# mp28164-buck-boost-flashlight-driver-tes.net
KiCad netlist of a schematic drawn in EAGLE
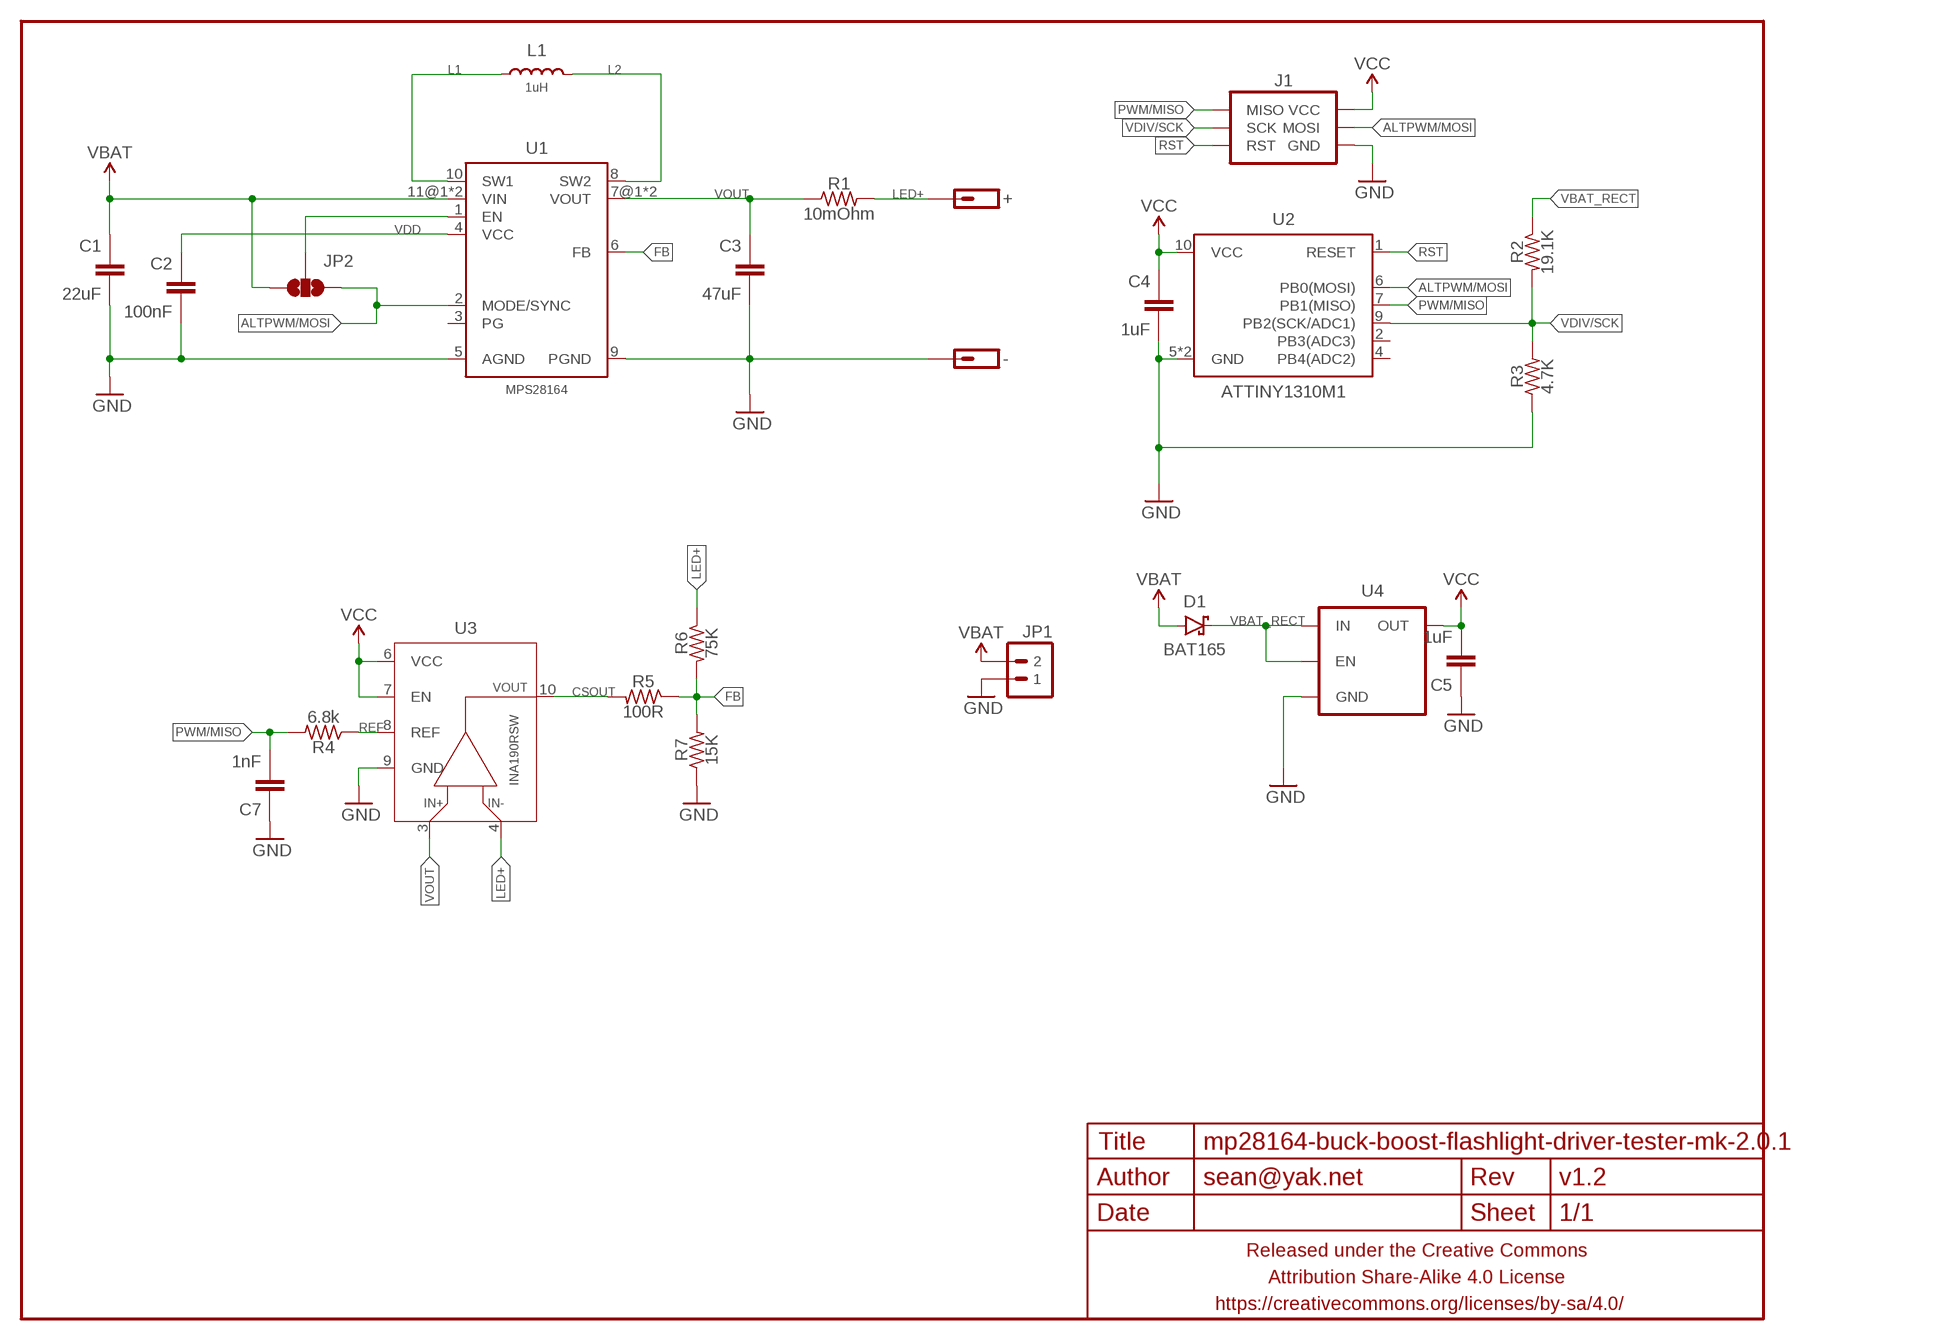
[diagram p0: schematic, sheet 1]

(export (version "E")
  (design (tool "Eeschema 10.0.6"))
  (components
    (comp (ref "+")
      (value "M01PTH-1.2MM-NS")
      (footprint "eagle-import:1X01-1.2MM-NS")
      (libsource (lib "eagle-import") (part "M01PTH-1.2MM-NS"))
    )
    (comp (ref "-")
      (value "M01PTH-1.2MM-NS")
      (footprint "eagle-import:1X01-1.2MM-NS")
      (libsource (lib "eagle-import") (part "M01PTH-1.2MM-NS"))
    )
    (comp (ref "C1")
      (value "22uF")
      (footprint "eagle-import:C1206")
      (libsource (lib "eagle-import") (part "CAPACITOR-CERAMICC1206"))
    )
    (comp (ref "C2")
      (value "100nF")
      (footprint "eagle-import:C0402")
      (libsource (lib "eagle-import") (part "CAPACITOR-CERAMICC0402"))
    )
    (comp (ref "C3")
      (value "47uF")
      (footprint "eagle-import:C1206")
      (libsource (lib "eagle-import") (part "CAPACITOR-CERAMICC1206"))
    )
    (comp (ref "C4")
      (value "1uF")
      (footprint "eagle-import:C0402")
      (libsource (lib "eagle-import") (part "CAPACITOR-CERAMICC0402"))
    )
    (comp (ref "C5")
      (value "1uF")
      (footprint "eagle-import:C0402")
      (libsource (lib "eagle-import") (part "CAPACITOR-CERAMICC0402"))
    )
    (comp (ref "C7")
      (value "1nF")
      (footprint "eagle-import:C0402")
      (libsource (lib "eagle-import") (part "CAPACITOR-CERAMICC0402"))
    )
    (comp (ref "D1")
      (value "BAT165")
      (footprint "eagle-import:SOD323-SCHOTTKY")
      (libsource (lib "eagle-import") (part "DIODE-SCHOTTKYSOD323"))
    )
    (comp (ref "FRAME1")
      (value "FRAME-LETTERNO_PACKAGE")
      (footprint "eagle-import:DUMMY")
      (fields
        (field (name "DESIGNER") "sean@yak.net")
        (field (name "VERSION") "v1.2")
        (field (name "DESIGNER_1") "sean@yak.net")
        (field (name "VERSION_1") "v1.2")
      )
      (libsource (lib "eagle-import") (part "FRAME-LETTERNO_PACKAGE"))
    )
    (comp (ref "J1")
      (value "AVR_SPI_PRG_6PTH")
      (footprint "eagle-import:2X3")
      (libsource (lib "eagle-import") (part "AVR_SPI_PRG_6PTH"))
    )
    (comp (ref "JP1")
      (value "M02PTH-CENTERED")
      (footprint "eagle-import:1X02-CENTER")
      (libsource (lib "eagle-import") (part "M02PTH-CENTERED"))
    )
    (comp (ref "JP2")
      (value "JUMPER-PAD-3-NOFULL_BOX_SILK")
      (footprint "eagle-import:PAD-JUMPER-3-NO_YES_SILK_FULL_BOX")
      (libsource (lib "eagle-import") (part "JUMPER-PAD-3-NOFULL_BOX_SILK"))
    )
    (comp (ref "L1")
      (value "1uH")
      (footprint "eagle-import:XAL60XX")
      (libsource (lib "eagle-import") (part "INDUCTORXAL60XX"))
    )
    (comp (ref "R1")
      (value "10mOhm")
      (footprint "eagle-import:R1206")
      (libsource (lib "eagle-import") (part "RESISTORR1206"))
    )
    (comp (ref "R2")
      (value "19.1K")
      (footprint "eagle-import:R0402")
      (libsource (lib "eagle-import") (part "RESISTORR0402"))
    )
    (comp (ref "R3")
      (value "4.7K")
      (footprint "eagle-import:R0402")
      (libsource (lib "eagle-import") (part "RESISTORR0402"))
    )
    (comp (ref "R4")
      (value "6.8k")
      (footprint "eagle-import:R0402")
      (libsource (lib "eagle-import") (part "RESISTORR0402"))
    )
    (comp (ref "R5")
      (value "100R")
      (footprint "eagle-import:R0402")
      (libsource (lib "eagle-import") (part "RESISTORR0402"))
    )
    (comp (ref "R6")
      (value "75K")
      (footprint "eagle-import:R0402")
      (libsource (lib "eagle-import") (part "RESISTORR0402"))
    )
    (comp (ref "R7")
      (value "15K")
      (footprint "eagle-import:R0402")
      (libsource (lib "eagle-import") (part "RESISTORR0402"))
    )
    (comp (ref "U1")
      (value "MPS28164")
      (footprint "eagle-import:MPS28164")
      (libsource (lib "eagle-import") (part "MPS28164"))
    )
    (comp (ref "U2")
      (value "ATTINY1310M1")
      (footprint "eagle-import:QFN10(2X5)")
      (libsource (lib "eagle-import") (part "ATTINY1310M1"))
    )
    (comp (ref "U3")
      (value "INA190RSW")
      (footprint "eagle-import:UQFN-10")
      (libsource (lib "eagle-import") (part "INA190RSW"))
    )
    (comp (ref "U4")
      (value "V_REG_ENTLV700")
      (footprint "eagle-import:SC70")
      (libsource (lib "eagle-import") (part "V_REG_ENTLV700"))
    )
  )
  (nets
    (net (code "1") (name "/CSOUT") (class "Default")
      (node (ref "R5") (pin "2") (pinfunction "2_2") (pintype "passive"))
      (node (ref "U3") (pin "10") (pinfunction "OUT_10") (pintype "bidirectional"))
    )
    (net (code "2") (name "/L1") (class "Default")
      (node (ref "L1") (pin "P$1") (pinfunction "1_P$1") (pintype "passive"))
      (node (ref "U1") (pin "10") (pinfunction "SW1_10") (pintype "bidirectional"))
    )
    (net (code "3") (name "/L2") (class "Default")
      (node (ref "L1") (pin "P$2") (pinfunction "2_P$2") (pintype "passive"))
      (node (ref "U1") (pin "8") (pinfunction "SW2_8") (pintype "bidirectional"))
    )
    (net (code "4") (name "/REF") (class "Default")
      (node (ref "R4") (pin "1") (pinfunction "1_1") (pintype "passive"))
      (node (ref "U3") (pin "8") (pinfunction "REF_8") (pintype "bidirectional"))
    )
    (net (code "5") (name "/VDD") (class "Default")
      (node (ref "C2") (pin "1") (pinfunction "1_1") (pintype "passive"))
      (node (ref "U1") (pin "4") (pinfunction "VCC_4") (pintype "bidirectional"))
    )
    (net (code "6") (name "ALTPWM{slash}MOSI") (class "Default")
      (node (ref "J1") (pin "4") (pinfunction "MOSI_4") (pintype "passive"))
      (node (ref "JP2") (pin "1") (pinfunction "1_1") (pintype "passive"))
      (node (ref "U1") (pin "2") (pinfunction "MODE/SYNC_2") (pintype "bidirectional"))
      (node (ref "U2") (pin "6") (pinfunction "PB0(MOSI)_6") (pintype "bidirectional"))
    )
    (net (code "7") (name "FB") (class "Default")
      (node (ref "R5") (pin "1") (pinfunction "1_1") (pintype "passive"))
      (node (ref "R6") (pin "2") (pinfunction "2_2") (pintype "passive"))
      (node (ref "R7") (pin "2") (pinfunction "2_2") (pintype "passive"))
      (node (ref "U1") (pin "6") (pinfunction "FB_6") (pintype "bidirectional"))
    )
    (net (code "8") (name "GND") (class "Default")
      (node (ref "-") (pin "P$1") (pinfunction "1_P$1") (pintype "passive"))
      (node (ref "C1") (pin "2") (pinfunction "2_2") (pintype "passive"))
      (node (ref "C2") (pin "2") (pinfunction "2_2") (pintype "passive"))
      (node (ref "C3") (pin "2") (pinfunction "2_2") (pintype "passive"))
      (node (ref "C4") (pin "2") (pinfunction "2_2") (pintype "passive"))
      (node (ref "C5") (pin "1") (pinfunction "1_1") (pintype "passive"))
      (node (ref "C7") (pin "1") (pinfunction "1_1") (pintype "passive"))
      (node (ref "J1") (pin "6") (pinfunction "GND_6") (pintype "passive"))
      (node (ref "JP1") (pin "1") (pinfunction "1_1") (pintype "passive"))
      (node (ref "R3") (pin "1") (pinfunction "1_1") (pintype "passive"))
      (node (ref "R7") (pin "1") (pinfunction "1_1") (pintype "passive"))
      (node (ref "U1") (pin "5") (pinfunction "AGND_5") (pintype "bidirectional"))
      (node (ref "U1") (pin "9") (pinfunction "PGND_9") (pintype "bidirectional"))
      (node (ref "U2") (pin "5") (pinfunction "GND_5") (pintype "bidirectional"))
      (node (ref "U2") (pin "PAD") (pinfunction "GND_PAD") (pintype "bidirectional"))
      (node (ref "U3") (pin "9") (pinfunction "GND_9") (pintype "bidirectional"))
      (node (ref "U4") (pin "2") (pinfunction "GND_2") (pintype "input"))
    )
    (net (code "9") (name "LED+") (class "Default")
      (node (ref "+") (pin "P$1") (pinfunction "1_P$1") (pintype "passive"))
      (node (ref "R1") (pin "2") (pinfunction "2_2") (pintype "passive"))
      (node (ref "R6") (pin "1") (pinfunction "1_1") (pintype "passive"))
      (node (ref "U3") (pin "4") (pinfunction "VIN-_4") (pintype "bidirectional"))
    )
    (net (code "10") (name "Net-(U1-EN)") (class "Default")
      (node (ref "JP2") (pin "2") (pinfunction "2_2") (pintype "passive"))
      (node (ref "U1") (pin "1") (pinfunction "EN_1") (pintype "bidirectional"))
    )
    (net (code "11") (name "PWM{slash}MISO") (class "Default")
      (node (ref "C7") (pin "2") (pinfunction "2_2") (pintype "passive"))
      (node (ref "J1") (pin "1") (pinfunction "MISO_1") (pintype "passive"))
      (node (ref "R4") (pin "2") (pinfunction "2_2") (pintype "passive"))
      (node (ref "U2") (pin "7") (pinfunction "PB1(MISO)_7") (pintype "bidirectional"))
    )
    (net (code "12") (name "RST") (class "Default")
      (node (ref "J1") (pin "5") (pinfunction "RST_5") (pintype "passive"))
      (node (ref "U2") (pin "1") (pinfunction "RESET_1") (pintype "bidirectional"))
    )
    (net (code "13") (name "VBAT") (class "Default")
      (node (ref "C1") (pin "1") (pinfunction "1_1") (pintype "passive"))
      (node (ref "D1") (pin "A") (pinfunction "A_A") (pintype "passive"))
      (node (ref "JP1") (pin "2") (pinfunction "2_2") (pintype "passive"))
      (node (ref "JP2") (pin "3") (pinfunction "3_3") (pintype "passive"))
      (node (ref "U1") (pin "11@1") (pinfunction "VIN_11@1") (pintype "bidirectional"))
      (node (ref "U1") (pin "11@2") (pinfunction "VIN_11@2") (pintype "bidirectional"))
    )
    (net (code "14") (name "VBAT_RECT") (class "Default")
      (node (ref "D1") (pin "C") (pinfunction "C_C") (pintype "passive"))
      (node (ref "R2") (pin "1") (pinfunction "1_1") (pintype "passive"))
      (node (ref "U4") (pin "1") (pinfunction "IN_1") (pintype "input"))
      (node (ref "U4") (pin "3") (pinfunction "EN_3") (pintype "input"))
    )
    (net (code "15") (name "VCC") (class "Default")
      (node (ref "C4") (pin "1") (pinfunction "1_1") (pintype "passive"))
      (node (ref "C5") (pin "2") (pinfunction "2_2") (pintype "passive"))
      (node (ref "J1") (pin "2") (pinfunction "VCC_2") (pintype "passive"))
      (node (ref "U2") (pin "10") (pinfunction "VCC_10") (pintype "bidirectional"))
      (node (ref "U3") (pin "6") (pinfunction "VCC_6") (pintype "bidirectional"))
      (node (ref "U3") (pin "7") (pinfunction "EN_7") (pintype "bidirectional"))
      (node (ref "U4") (pin "5") (pinfunction "OUT_5") (pintype "passive"))
    )
    (net (code "16") (name "VDIV{slash}SCK") (class "Default")
      (node (ref "J1") (pin "3") (pinfunction "SCK_3") (pintype "passive"))
      (node (ref "R2") (pin "2") (pinfunction "2_2") (pintype "passive"))
      (node (ref "R3") (pin "2") (pinfunction "2_2") (pintype "passive"))
      (node (ref "U2") (pin "9") (pinfunction "PB2(SCK/ADC1)_9") (pintype "bidirectional"))
    )
    (net (code "17") (name "VOUT") (class "Default")
      (node (ref "C3") (pin "1") (pinfunction "1_1") (pintype "passive"))
      (node (ref "R1") (pin "1") (pinfunction "1_1") (pintype "passive"))
      (node (ref "U1") (pin "7@1") (pinfunction "VOUT_7@1") (pintype "bidirectional"))
      (node (ref "U1") (pin "7@2") (pinfunction "VOUT_7@2") (pintype "bidirectional"))
      (node (ref "U3") (pin "3") (pinfunction "VIN+_3") (pintype "bidirectional"))
    )
    (net (code "18") (name "unconnected-(U1-PG-Pad3)") (class "Default")
      (node (ref "U1") (pin "3") (pinfunction "PG_3") (pintype "bidirectional"))
    )
    (net (code "19") (name "unconnected-(U2-PB3(ADC3)-Pad2)") (class "Default")
      (node (ref "U2") (pin "2") (pinfunction "PB3(ADC3)_2") (pintype "bidirectional"))
    )
    (net (code "20") (name "unconnected-(U2-PB4(ADC2)-Pad4)") (class "Default")
      (node (ref "U2") (pin "4") (pinfunction "PB4(ADC2)_4") (pintype "bidirectional"))
    )
  )
)
